# Test_Plates_-_SMD_to_PLS_Adapters.net
KiCad netlist of a schematic drawn in Altium Designer
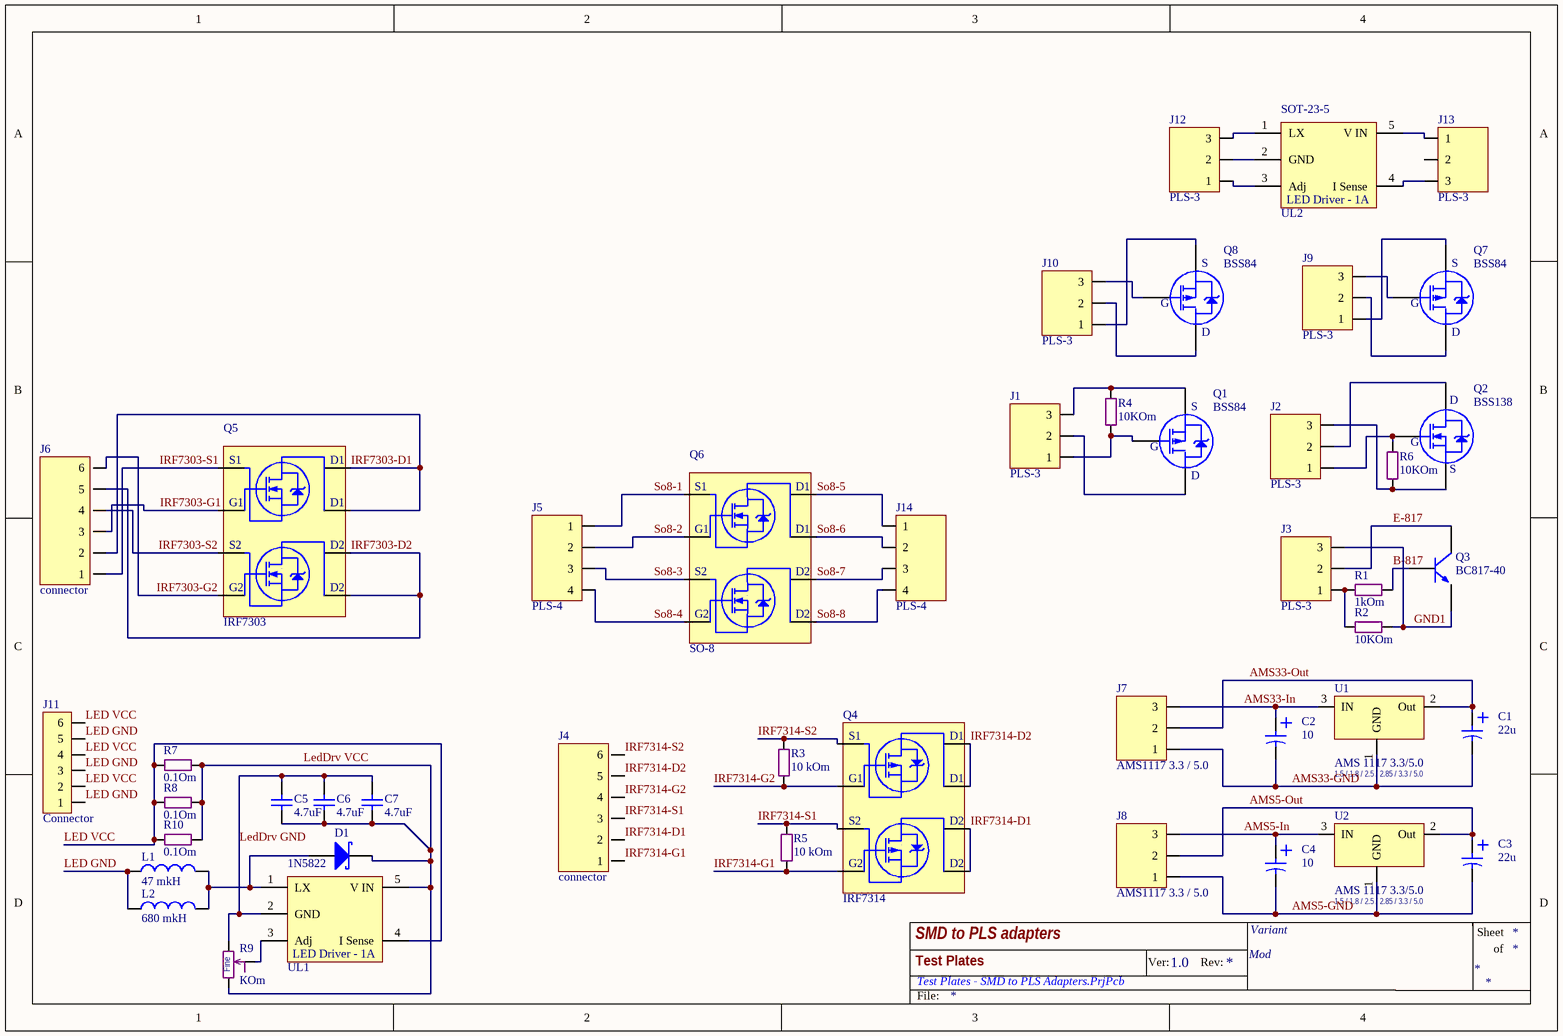
[diagram p0: Test Plates - SMD to PLS Adapters.SchDoc]

(export (version "E")
  (design (tool "Eeschema 10.0.6"))
  (components
    (comp (ref "C1")
      (value "22u")
      (footprint "Capacitor:SMD 3528 Tantal (1210)")
      (description "Capacitor")
      (libsource (lib "Capacitor") (part "Cap Tantal"))
    )
    (comp (ref "C2")
      (value "10")
      (footprint "Capacitor:SMD 1206 Tantal (3216)")
      (description "Capacitor")
      (libsource (lib "Capacitor") (part "Cap Tantal"))
    )
    (comp (ref "C3")
      (value "22u")
      (footprint "Capacitor:SMD 3528 Tantal (1210)")
      (description "Capacitor")
      (libsource (lib "Capacitor") (part "Cap Tantal"))
    )
    (comp (ref "C4")
      (value "10")
      (footprint "Capacitor:SMD 1206 Tantal (3216)")
      (description "Capacitor")
      (libsource (lib "Capacitor") (part "Cap Tantal"))
    )
    (comp (ref "C5")
      (value "4.7uF")
      (footprint "Capacitor:SMD 0805 (2012)")
      (description "Capacitor")
      (libsource (lib "Capacitor") (part "Cap SMD 0402-1812"))
    )
    (comp (ref "C6")
      (value "4.7uF")
      (footprint "Capacitor:SMD 1206 (3216)")
      (description "Capacitor")
      (libsource (lib "Capacitor") (part "Cap SMD 0402-1812"))
    )
    (comp (ref "C7")
      (value "4.7uF")
      (footprint "Capacitor:Cap p2.54mm (2p)")
      (description "Capacitor")
      (libsource (lib "Capacitor") (part "Cap Ceramic"))
    )
    (comp (ref "D1")
      (value "1N5822")
      (footprint "Diodes:Diode DO-41")
      (description "Shotki  Diode")
      (libsource (lib "Diodes") (part "D Shotki All"))
    )
    (comp (ref "J1")
      (value "PLS-3")
      (footprint "Connector:Line 2.54 X 3")
      (description "Vert, Sgl line, Male")
      (libsource (lib "Connector") (part "PLS-3"))
    )
    (comp (ref "J2")
      (value "PLS-3")
      (footprint "Connector:Line 2.54 X 3")
      (description "Vert, Sgl line, Male")
      (libsource (lib "Connector") (part "PLS-3"))
    )
    (comp (ref "J3")
      (value "PLS-3")
      (footprint "Connector:Line 2.54 X 3")
      (description "Vert, Sgl line, Male")
      (libsource (lib "Connector") (part "PLS-3"))
    )
    (comp (ref "J4")
      (value "connector")
      (footprint "Connector:Line 2.54 x 6")
      (description "Vert, Sgl line, Male")
      (libsource (lib "Connector") (part "PLS-6"))
    )
    (comp (ref "J5")
      (value "PLS-4")
      (footprint "Connector:Line 2.54 X 4")
      (description "Vert, Sgl line, Male")
      (libsource (lib "Connector") (part "PLS-4"))
    )
    (comp (ref "J6")
      (value "connector")
      (footprint "Connector:Line 2.54 x 6")
      (description "Vert, Sgl line, Male")
      (libsource (lib "Connector") (part "PLS-6"))
    )
    (comp (ref "J7")
      (value "AMS1117 3.3 / 5.0")
      (footprint "Connector:Line 2.54 X 3")
      (description "Vert, Sgl line, Male")
      (libsource (lib "Connector") (part "PLS-3"))
    )
    (comp (ref "J8")
      (value "AMS1117 3.3 / 5.0")
      (footprint "Connector:Line 2.54 X 3")
      (description "Vert, Sgl line, Male")
      (libsource (lib "Connector") (part "PLS-3"))
    )
    (comp (ref "J9")
      (value "PLS-3")
      (footprint "Connector:Line 2.54 X 3")
      (description "Vert, Sgl line, Male")
      (libsource (lib "Connector") (part "PLS-3"))
    )
    (comp (ref "J10")
      (value "PLS-3")
      (footprint "Connector:Line 2.54 X 3")
      (description "Vert, Sgl line, Male")
      (libsource (lib "Connector") (part "PLS-3"))
    )
    (comp (ref "J11")
      (value "Connector")
      (footprint "Connector:LINE 2.54 x 6D (2 x 3)")
      (description "Vert, Dbl line, Male")
      (libsource (lib "Connector") (part "PLD-6 (2 x 3)"))
    )
    (comp (ref "J12")
      (value "PLS-3")
      (footprint "Connector:Line 2.54 X 3")
      (description "Vert, Sgl line, Male")
      (libsource (lib "Connector") (part "PLS-3"))
    )
    (comp (ref "J13")
      (value "PLS-3")
      (footprint "Connector:Line 2.54 X 3")
      (description "Vert, Sgl line, Male")
      (libsource (lib "") (part "PLS-3_1"))
    )
    (comp (ref "J14")
      (value "PLS-4")
      (footprint "Connector:Line 2.54 X 4")
      (description "Vert, Sgl line, Male")
      (libsource (lib "") (part "PLS-4_1"))
    )
    (comp (ref "L1")
      (value "47 mkH")
      (footprint "Transformers:47 mkH")
      (description "Inductor")
      (libsource (lib "Transformers") (part "Inductor 47 mkH"))
    )
    (comp (ref "L2")
      (value "680 mkH")
      (footprint "Transformers:680 mkH")
      (description "Inductor")
      (libsource (lib "Transformers") (part "Inductor 680mkH"))
    )
    (comp (ref "Q1")
      (value "BSS84")
      (footprint "GeneralCases:SOT-23")
      (description "P-Channel -50V - 10-1Ω - 0.13A")
      (libsource (lib "") (part "BSS84_1"))
    )
    (comp (ref "Q2")
      (value "BSS138")
      (footprint "GeneralCases:SOT-23")
      (description "N-Channel 50V - 0.7-1Ω - 0.22A")
      (libsource (lib "Transistor") (part "BSS138"))
    )
    (comp (ref "Q3")
      (value "BC817-40")
      (footprint "GeneralCases:SOT-23")
      (description "NPN 45 V, 500 mA NPN general-purpose transistor")
      (libsource (lib "Transistor") (part "BC817-40"))
    )
    (comp (ref "Q4")
      (value "IRF7314")
      (footprint "GeneralCases:SO8")
      (description "Dual P-Ch  20V - 0.058Ω - 5.3A")
      (libsource (lib "Transistor") (part "IRF7314"))
    )
    (comp (ref "Q5")
      (value "IRF7303")
      (footprint "GeneralCases:SO8")
      (description "Dual N-Ch  30V - 0.05Ω - 4.9A")
      (fields (field (name "MANUFACTURER") "Farchild"))
      (libsource (lib "Transistor") (part "IRF7303"))
    )
    (comp (ref "Q6")
      (value "SO-8")
      (footprint "GeneralCases:SO8")
      (description "Dual N-Ch  30V - 0.05Ω - 4.9A")
      (fields (field (name "MANUFACTURER") "Farchild"))
      (libsource (lib "Transistor") (part "IRF7303"))
    )
    (comp (ref "Q7")
      (value "BSS84")
      (footprint "GeneralCases:SOT-23")
      (description "P-Channel -50V - 10-1Ω - 0.13A")
      (libsource (lib "Transistor") (part "BSS84"))
    )
    (comp (ref "Q8")
      (value "BSS84")
      (footprint "GeneralCases:SOT-23")
      (description "P-Channel -50V - 10-1Ω - 0.13A")
      (libsource (lib "") (part "BSS84_1"))
    )
    (comp (ref "R1")
      (value "1kOm")
      (footprint "PassiveComponents:SMD 0603 (1608)")
      (libsource (lib "PassiveComponents") (part "Res SMD 0603"))
    )
    (comp (ref "R2")
      (value "10KOm")
      (footprint "PassiveComponents:SMD 0603 (1608)")
      (libsource (lib "PassiveComponents") (part "Res SMD 0603"))
    )
    (comp (ref "R3")
      (value "10 kOm")
      (footprint "PassiveComponents:SMD 0805 (2012)")
      (libsource (lib "PassiveComponents") (part "Res All Types"))
    )
    (comp (ref "R4")
      (value "10KOm")
      (footprint "PassiveComponents:SMD 0603 (1608)")
      (libsource (lib "PassiveComponents") (part "Res SMD 0603"))
    )
    (comp (ref "R5")
      (value "10 kOm")
      (footprint "PassiveComponents:SMD 0805 (2012)")
      (libsource (lib "PassiveComponents") (part "Res All Types"))
    )
    (comp (ref "R6")
      (value "10KOm")
      (footprint "PassiveComponents:SMD 0603 (1608)")
      (libsource (lib "PassiveComponents") (part "Res SMD 0603"))
    )
    (comp (ref "R7")
      (value "0.1Om")
      (footprint "PassiveComponents:SMD 0805 (2012)")
      (libsource (lib "PassiveComponents") (part "Res All Types"))
    )
    (comp (ref "R8")
      (value "0.1Om")
      (footprint "PassiveComponents:Res 2W p15.24")
      (libsource (lib "PassiveComponents") (part "Res All Types"))
    )
    (comp (ref "R9")
      (value "КOm")
      (footprint "PassiveComponents:Res Adj 3296 Univ")
      (libsource (lib "PassiveComponents") (part "Res Adj 3296"))
    )
    (comp (ref "R10")
      (value "0.1Om")
      (footprint "PassiveComponents:SMD 0805 (2012)")
      (libsource (lib "PassiveComponents") (part "Res All Types"))
    )
    (comp (ref "U1")
      (value "AMS 1117 3.3/5.0")
      (footprint "GeneralCases:SOT-223-3 (AMS)")
      (description "Voltage Regulator SOT-223-3")
      (fields (field (name "V OUT") "1.5 / 1.8 / 2.5 / 2.85 / 3.3 / 5.0"))
      (libsource (lib "PowerAdjusment") (part "AMS1117_FIX"))
    )
    (comp (ref "U2")
      (value "AMS 1117 3.3/5.0")
      (footprint "GeneralCases:SOT-223-3 (AMS)")
      (description "Voltage Regulator SOT-223-3")
      (fields (field (name "V OUT") "1.5 / 1.8 / 2.5 / 2.85 / 3.3 / 5.0"))
      (libsource (lib "PowerAdjusment") (part "AMS1117_FIX"))
    )
    (comp (ref "UL1")
      (value "ZXLD1360ET5TA")
      (footprint "GeneralCases:SOT-23-5")
      (description "Led Driver - 1A, 7-30V In")
      (libsource (lib "Chips") (part "ZXLD1360ET5TA"))
    )
    (comp (ref "UL2")
      (value "SOT-23-5")
      (footprint "GeneralCases:SOT-23-5")
      (description "Led Driver - 1A, 7-30V In")
      (libsource (lib "Chips") (part "ZXLD1360ET5TA"))
    )
  )
  (nets
    (net (code "1") (name "/AMS5-GND") (class "Default")
      (node (ref "C3") (pin "GND") (pinfunction "2_GND") (pintype "passive"))
      (node (ref "C4") (pin "GND") (pinfunction "2_GND") (pintype "passive"))
      (node (ref "J8") (pin "1") (pinfunction "1_1") (pintype "passive"))
      (node (ref "U2") (pin "1") (pinfunction "GND_1") (pintype "passive"))
    )
    (net (code "2") (name "/AMS5-In") (class "Default")
      (node (ref "C4") (pin "VCC") (pinfunction "1_VCC") (pintype "passive"))
      (node (ref "J8") (pin "3") (pinfunction "3_3") (pintype "passive"))
      (node (ref "U2") (pin "3") (pinfunction "IN_3") (pintype "power_in"))
    )
    (net (code "3") (name "/AMS5-Out") (class "Default")
      (node (ref "C3") (pin "VCC") (pinfunction "1_VCC") (pintype "passive"))
      (node (ref "J8") (pin "2") (pinfunction "2_2") (pintype "passive"))
      (node (ref "U2") (pin "2") (pinfunction "Out_2") (pintype "power_in"))
    )
    (net (code "4") (name "/AMS33-GND") (class "Default")
      (node (ref "C1") (pin "GND") (pinfunction "2_GND") (pintype "passive"))
      (node (ref "C2") (pin "GND") (pinfunction "2_GND") (pintype "passive"))
      (node (ref "J7") (pin "1") (pinfunction "1_1") (pintype "passive"))
      (node (ref "U1") (pin "1") (pinfunction "GND_1") (pintype "passive"))
    )
    (net (code "5") (name "/AMS33-In") (class "Default")
      (node (ref "C2") (pin "VCC") (pinfunction "1_VCC") (pintype "passive"))
      (node (ref "J7") (pin "3") (pinfunction "3_3") (pintype "passive"))
      (node (ref "U1") (pin "3") (pinfunction "IN_3") (pintype "power_in"))
    )
    (net (code "6") (name "/AMS33-Out") (class "Default")
      (node (ref "C1") (pin "VCC") (pinfunction "1_VCC") (pintype "passive"))
      (node (ref "J7") (pin "2") (pinfunction "2_2") (pintype "passive"))
      (node (ref "U1") (pin "2") (pinfunction "Out_2") (pintype "power_in"))
    )
    (net (code "7") (name "/B-817") (class "Default")
      (node (ref "Q3") (pin "1") (pinfunction "B_1") (pintype "passive"))
      (node (ref "R1") (pin "2") (pinfunction "2_2") (pintype "passive"))
    )
    (net (code "8") (name "/E-817") (class "Default")
      (node (ref "J3") (pin "2") (pinfunction "2_2") (pintype "passive"))
      (node (ref "Q3") (pin "3") (pinfunction "C_3") (pintype "passive"))
    )
    (net (code "9") (name "/GND1") (class "Default")
      (node (ref "J3") (pin "3") (pinfunction "3_3") (pintype "passive"))
      (node (ref "Q3") (pin "2") (pinfunction "E_2") (pintype "passive"))
      (node (ref "R2") (pin "2") (pinfunction "2_2") (pintype "passive"))
    )
    (net (code "10") (name "/IRF7303-D1") (class "Default")
      (node (ref "J6") (pin "2") (pinfunction "2_2") (pintype "passive"))
      (node (ref "Q5") (pin "7") (pinfunction "D_7") (pintype "passive"))
      (node (ref "Q5") (pin "8") (pinfunction "D_8") (pintype "passive"))
    )
    (net (code "11") (name "/IRF7303-D2") (class "Default")
      (node (ref "J6") (pin "5") (pinfunction "5_5") (pintype "passive"))
      (node (ref "Q5") (pin "5") (pinfunction "D_5") (pintype "passive"))
      (node (ref "Q5") (pin "6") (pinfunction "D_6") (pintype "passive"))
    )
    (net (code "12") (name "/IRF7303-G1") (class "Default")
      (node (ref "J6") (pin "3") (pinfunction "3_3") (pintype "passive"))
      (node (ref "Q5") (pin "2") (pinfunction "G_2") (pintype "passive"))
    )
    (net (code "13") (name "/IRF7303-G2") (class "Default")
      (node (ref "J6") (pin "6") (pinfunction "6_6") (pintype "passive"))
      (node (ref "Q5") (pin "4") (pinfunction "G_4") (pintype "passive"))
    )
    (net (code "14") (name "/IRF7303-S1") (class "Default")
      (node (ref "J6") (pin "1") (pinfunction "1_1") (pintype "passive"))
      (node (ref "Q5") (pin "1") (pinfunction "S_1") (pintype "passive"))
    )
    (net (code "15") (name "/IRF7303-S2") (class "Default")
      (node (ref "J6") (pin "4") (pinfunction "4_4") (pintype "passive"))
      (node (ref "Q5") (pin "3") (pinfunction "S_3") (pintype "passive"))
    )
    (net (code "16") (name "/IRF7314-D1") (class "Default")
      (node (ref "J4") (pin "2") (pinfunction "2_2") (pintype "passive"))
      (node (ref "Q4") (pin "5") (pinfunction "D_5") (pintype "passive"))
      (node (ref "Q4") (pin "6") (pinfunction "D_6") (pintype "passive"))
    )
    (net (code "17") (name "/IRF7314-D2") (class "Default")
      (node (ref "J4") (pin "5") (pinfunction "5_5") (pintype "passive"))
      (node (ref "Q4") (pin "7") (pinfunction "D_7") (pintype "passive"))
      (node (ref "Q4") (pin "8") (pinfunction "D_8") (pintype "passive"))
    )
    (net (code "18") (name "/IRF7314-G1") (class "Default")
      (node (ref "J4") (pin "1") (pinfunction "1_1") (pintype "passive"))
      (node (ref "Q4") (pin "4") (pinfunction "G_4") (pintype "passive"))
      (node (ref "R5") (pin "1") (pinfunction "1_1") (pintype "passive"))
    )
    (net (code "19") (name "/IRF7314-G2") (class "Default")
      (node (ref "J4") (pin "4") (pinfunction "4_4") (pintype "passive"))
      (node (ref "Q4") (pin "2") (pinfunction "G_2") (pintype "passive"))
      (node (ref "R3") (pin "1") (pinfunction "1_1") (pintype "passive"))
    )
    (net (code "20") (name "/IRF7314-S1") (class "Default")
      (node (ref "J4") (pin "3") (pinfunction "3_3") (pintype "passive"))
      (node (ref "Q4") (pin "3") (pinfunction "S_3") (pintype "passive"))
      (node (ref "R5") (pin "2") (pinfunction "2_2") (pintype "passive"))
    )
    (net (code "21") (name "/IRF7314-S2") (class "Default")
      (node (ref "J4") (pin "6") (pinfunction "6_6") (pintype "passive"))
      (node (ref "Q4") (pin "1") (pinfunction "S_1") (pintype "passive"))
      (node (ref "R3") (pin "2") (pinfunction "2_2") (pintype "passive"))
    )
    (net (code "22") (name "/LED GND") (class "Default")
      (node (ref "J11") (pin "1") (pinfunction "1_1") (pintype "passive"))
      (node (ref "J11") (pin "3") (pinfunction "3_3") (pintype "passive"))
      (node (ref "J11") (pin "5") (pinfunction "5_5") (pintype "passive"))
      (node (ref "L1") (pin "1") (pinfunction "1_1") (pintype "passive"))
      (node (ref "L2") (pin "1") (pinfunction "1_1") (pintype "passive"))
    )
    (net (code "23") (name "/LED VCC") (class "Default")
      (node (ref "J11") (pin "2") (pinfunction "2_2") (pintype "passive"))
      (node (ref "J11") (pin "4") (pinfunction "4_4") (pintype "passive"))
      (node (ref "J11") (pin "6") (pinfunction "6_6") (pintype "passive"))
      (node (ref "R10") (pin "1") (pinfunction "1_1") (pintype "passive"))
      (node (ref "R7") (pin "1") (pinfunction "1_1") (pintype "passive"))
      (node (ref "R8") (pin "1") (pinfunction "1_1") (pintype "passive"))
      (node (ref "UL1") (pin "4") (pinfunction "I_Sense_4") (pintype "power_in"))
    )
    (net (code "24") (name "/LedDrv GND") (class "Default")
      (node (ref "C5") (pin "1") (pinfunction "1_1") (pintype "passive"))
      (node (ref "C6") (pin "1") (pinfunction "1_1") (pintype "passive"))
      (node (ref "C7") (pin "1") (pinfunction "1_1") (pintype "passive"))
      (node (ref "R9") (pin "3") (pinfunction "3_3") (pintype "passive"))
      (node (ref "UL1") (pin "2") (pinfunction "GND_2") (pintype "tri_state"))
    )
    (net (code "25") (name "/LedDrv VCC") (class "Default")
      (node (ref "C5") (pin "2") (pinfunction "2_2") (pintype "passive"))
      (node (ref "C6") (pin "2") (pinfunction "2_2") (pintype "passive"))
      (node (ref "C7") (pin "2") (pinfunction "2_2") (pintype "passive"))
      (node (ref "D1") (pin "K") (pinfunction "K_K") (pintype "passive"))
      (node (ref "R10") (pin "2") (pinfunction "2_2") (pintype "passive"))
      (node (ref "R7") (pin "2") (pinfunction "2_2") (pintype "passive"))
      (node (ref "R8") (pin "2") (pinfunction "2_2") (pintype "passive"))
      (node (ref "R9") (pin "1") (pinfunction "1_1") (pintype "passive"))
      (node (ref "UL1") (pin "5") (pinfunction "V_IN_5") (pintype "tri_state"))
    )
    (net (code "26") (name "/So8-1") (class "Default")
      (node (ref "J5") (pin "1") (pinfunction "1_1") (pintype "passive"))
      (node (ref "Q6") (pin "1") (pinfunction "S_1") (pintype "passive"))
    )
    (net (code "27") (name "/So8-2") (class "Default")
      (node (ref "J5") (pin "2") (pinfunction "2_2") (pintype "passive"))
      (node (ref "Q6") (pin "2") (pinfunction "G_2") (pintype "passive"))
    )
    (net (code "28") (name "/So8-3") (class "Default")
      (node (ref "J5") (pin "3") (pinfunction "3_3") (pintype "passive"))
      (node (ref "Q6") (pin "3") (pinfunction "S_3") (pintype "passive"))
    )
    (net (code "29") (name "/So8-4") (class "Default")
      (node (ref "J5") (pin "4") (pinfunction "4_4") (pintype "passive"))
      (node (ref "Q6") (pin "4") (pinfunction "G_4") (pintype "passive"))
    )
    (net (code "30") (name "/So8-5") (class "Default")
      (node (ref "J14") (pin "1") (pinfunction "1_1") (pintype "passive"))
      (node (ref "Q6") (pin "8") (pinfunction "D_8") (pintype "passive"))
    )
    (net (code "31") (name "/So8-6") (class "Default")
      (node (ref "J14") (pin "2") (pinfunction "2_2") (pintype "passive"))
      (node (ref "Q6") (pin "7") (pinfunction "D_7") (pintype "passive"))
    )
    (net (code "32") (name "/So8-7") (class "Default")
      (node (ref "J14") (pin "3") (pinfunction "3_3") (pintype "passive"))
      (node (ref "Q6") (pin "6") (pinfunction "D_6") (pintype "passive"))
    )
    (net (code "33") (name "/So8-8") (class "Default")
      (node (ref "J14") (pin "4") (pinfunction "4_4") (pintype "passive"))
      (node (ref "Q6") (pin "5") (pinfunction "D_5") (pintype "passive"))
    )
    (net (code "34") (name "Net-(J3-Pad1)") (class "Default")
      (node (ref "J3") (pin "1") (pinfunction "1_1") (pintype "passive"))
      (node (ref "R1") (pin "1") (pinfunction "1_1") (pintype "passive"))
      (node (ref "R2") (pin "1") (pinfunction "1_1") (pintype "passive"))
    )
    (net (code "35") (name "Net-(Q1-D)") (class "Default")
      (node (ref "J1") (pin "2") (pinfunction "2_2") (pintype "passive"))
      (node (ref "Q1") (pin "3") (pinfunction "D_3") (pintype "passive"))
    )
    (net (code "36") (name "Net-(Q1-G)") (class "Default")
      (node (ref "J1") (pin "1") (pinfunction "1_1") (pintype "passive"))
      (node (ref "Q1") (pin "1") (pinfunction "G_1") (pintype "passive"))
      (node (ref "R4") (pin "1") (pinfunction "1_1") (pintype "passive"))
    )
    (net (code "37") (name "Net-(Q1-S)") (class "Default")
      (node (ref "J1") (pin "3") (pinfunction "3_3") (pintype "passive"))
      (node (ref "Q1") (pin "2") (pinfunction "S_2") (pintype "passive"))
      (node (ref "R4") (pin "2") (pinfunction "2_2") (pintype "passive"))
    )
    (net (code "38") (name "Net-(Q2-D)") (class "Default")
      (node (ref "J2") (pin "2") (pinfunction "2_2") (pintype "passive"))
      (node (ref "Q2") (pin "2") (pinfunction "D_2") (pintype "passive"))
    )
    (net (code "39") (name "Net-(Q2-G)") (class "Default")
      (node (ref "J2") (pin "1") (pinfunction "1_1") (pintype "passive"))
      (node (ref "Q2") (pin "1") (pinfunction "G_1") (pintype "passive"))
      (node (ref "R6") (pin "2") (pinfunction "2_2") (pintype "passive"))
    )
    (net (code "40") (name "Net-(Q2-S)") (class "Default")
      (node (ref "J2") (pin "3") (pinfunction "3_3") (pintype "passive"))
      (node (ref "Q2") (pin "3") (pinfunction "S_3") (pintype "passive"))
      (node (ref "R6") (pin "1") (pinfunction "1_1") (pintype "passive"))
    )
    (net (code "41") (name "Net-(Q7-D)") (class "Default")
      (node (ref "J9") (pin "2") (pinfunction "2_2") (pintype "passive"))
      (node (ref "Q7") (pin "3") (pinfunction "D_3") (pintype "passive"))
    )
    (net (code "42") (name "Net-(Q7-G)") (class "Default")
      (node (ref "J9") (pin "3") (pinfunction "3_3") (pintype "passive"))
      (node (ref "Q7") (pin "1") (pinfunction "G_1") (pintype "passive"))
    )
    (net (code "43") (name "Net-(Q7-S)") (class "Default")
      (node (ref "J9") (pin "1") (pinfunction "1_1") (pintype "passive"))
      (node (ref "Q7") (pin "2") (pinfunction "S_2") (pintype "passive"))
    )
    (net (code "44") (name "Net-(Q8-D)") (class "Default")
      (node (ref "J10") (pin "2") (pinfunction "2_2") (pintype "passive"))
      (node (ref "Q8") (pin "3") (pinfunction "D_3") (pintype "passive"))
    )
    (net (code "45") (name "Net-(Q8-G)") (class "Default")
      (node (ref "J10") (pin "3") (pinfunction "3_3") (pintype "passive"))
      (node (ref "Q8") (pin "1") (pinfunction "G_1") (pintype "passive"))
    )
    (net (code "46") (name "Net-(Q8-S)") (class "Default")
      (node (ref "J10") (pin "1") (pinfunction "1_1") (pintype "passive"))
      (node (ref "Q8") (pin "2") (pinfunction "S_2") (pintype "passive"))
    )
    (net (code "47") (name "Net-(UL1-Adj)") (class "Default")
      (node (ref "R9") (pin "2") (pinfunction "2_2") (pintype "passive"))
      (node (ref "UL1") (pin "3") (pinfunction "Adj_3") (pintype "power_in"))
    )
    (net (code "48") (name "Net-(UL1-LX)") (class "Default")
      (node (ref "D1") (pin "A") (pinfunction "A_A") (pintype "passive"))
      (node (ref "L1") (pin "2") (pinfunction "2_2") (pintype "passive"))
      (node (ref "L2") (pin "2") (pinfunction "2_2") (pintype "passive"))
      (node (ref "UL1") (pin "1") (pinfunction "LX_1") (pintype "power_in"))
    )
    (net (code "49") (name "Net-(UL2-Adj)") (class "Default")
      (node (ref "J12") (pin "1") (pinfunction "1_1") (pintype "passive"))
      (node (ref "UL2") (pin "3") (pinfunction "Adj_3") (pintype "power_in"))
    )
    (net (code "50") (name "Net-(UL2-GND)") (class "Default")
      (node (ref "J12") (pin "2") (pinfunction "2_2") (pintype "passive"))
      (node (ref "UL2") (pin "2") (pinfunction "GND_2") (pintype "tri_state"))
    )
    (net (code "51") (name "Net-(UL2-I_Sense)") (class "Default")
      (node (ref "J13") (pin "3") (pinfunction "3_3") (pintype "passive"))
      (node (ref "UL2") (pin "4") (pinfunction "I_Sense_4") (pintype "power_in"))
    )
    (net (code "52") (name "Net-(UL2-LX)") (class "Default")
      (node (ref "J12") (pin "3") (pinfunction "3_3") (pintype "passive"))
      (node (ref "UL2") (pin "1") (pinfunction "LX_1") (pintype "power_in"))
    )
    (net (code "53") (name "Net-(UL2-V_IN)") (class "Default")
      (node (ref "J13") (pin "1") (pinfunction "1_1") (pintype "passive"))
      (node (ref "UL2") (pin "5") (pinfunction "V_IN_5") (pintype "tri_state"))
    )
    (net (code "54") (name "unconnected-(J13-Pad2)") (class "Default")
      (node (ref "J13") (pin "2") (pinfunction "2_2") (pintype "passive"))
    )
  )
)
